# usb2can.net
KiCad netlist of a schematic drawn in EasyEDA Pro
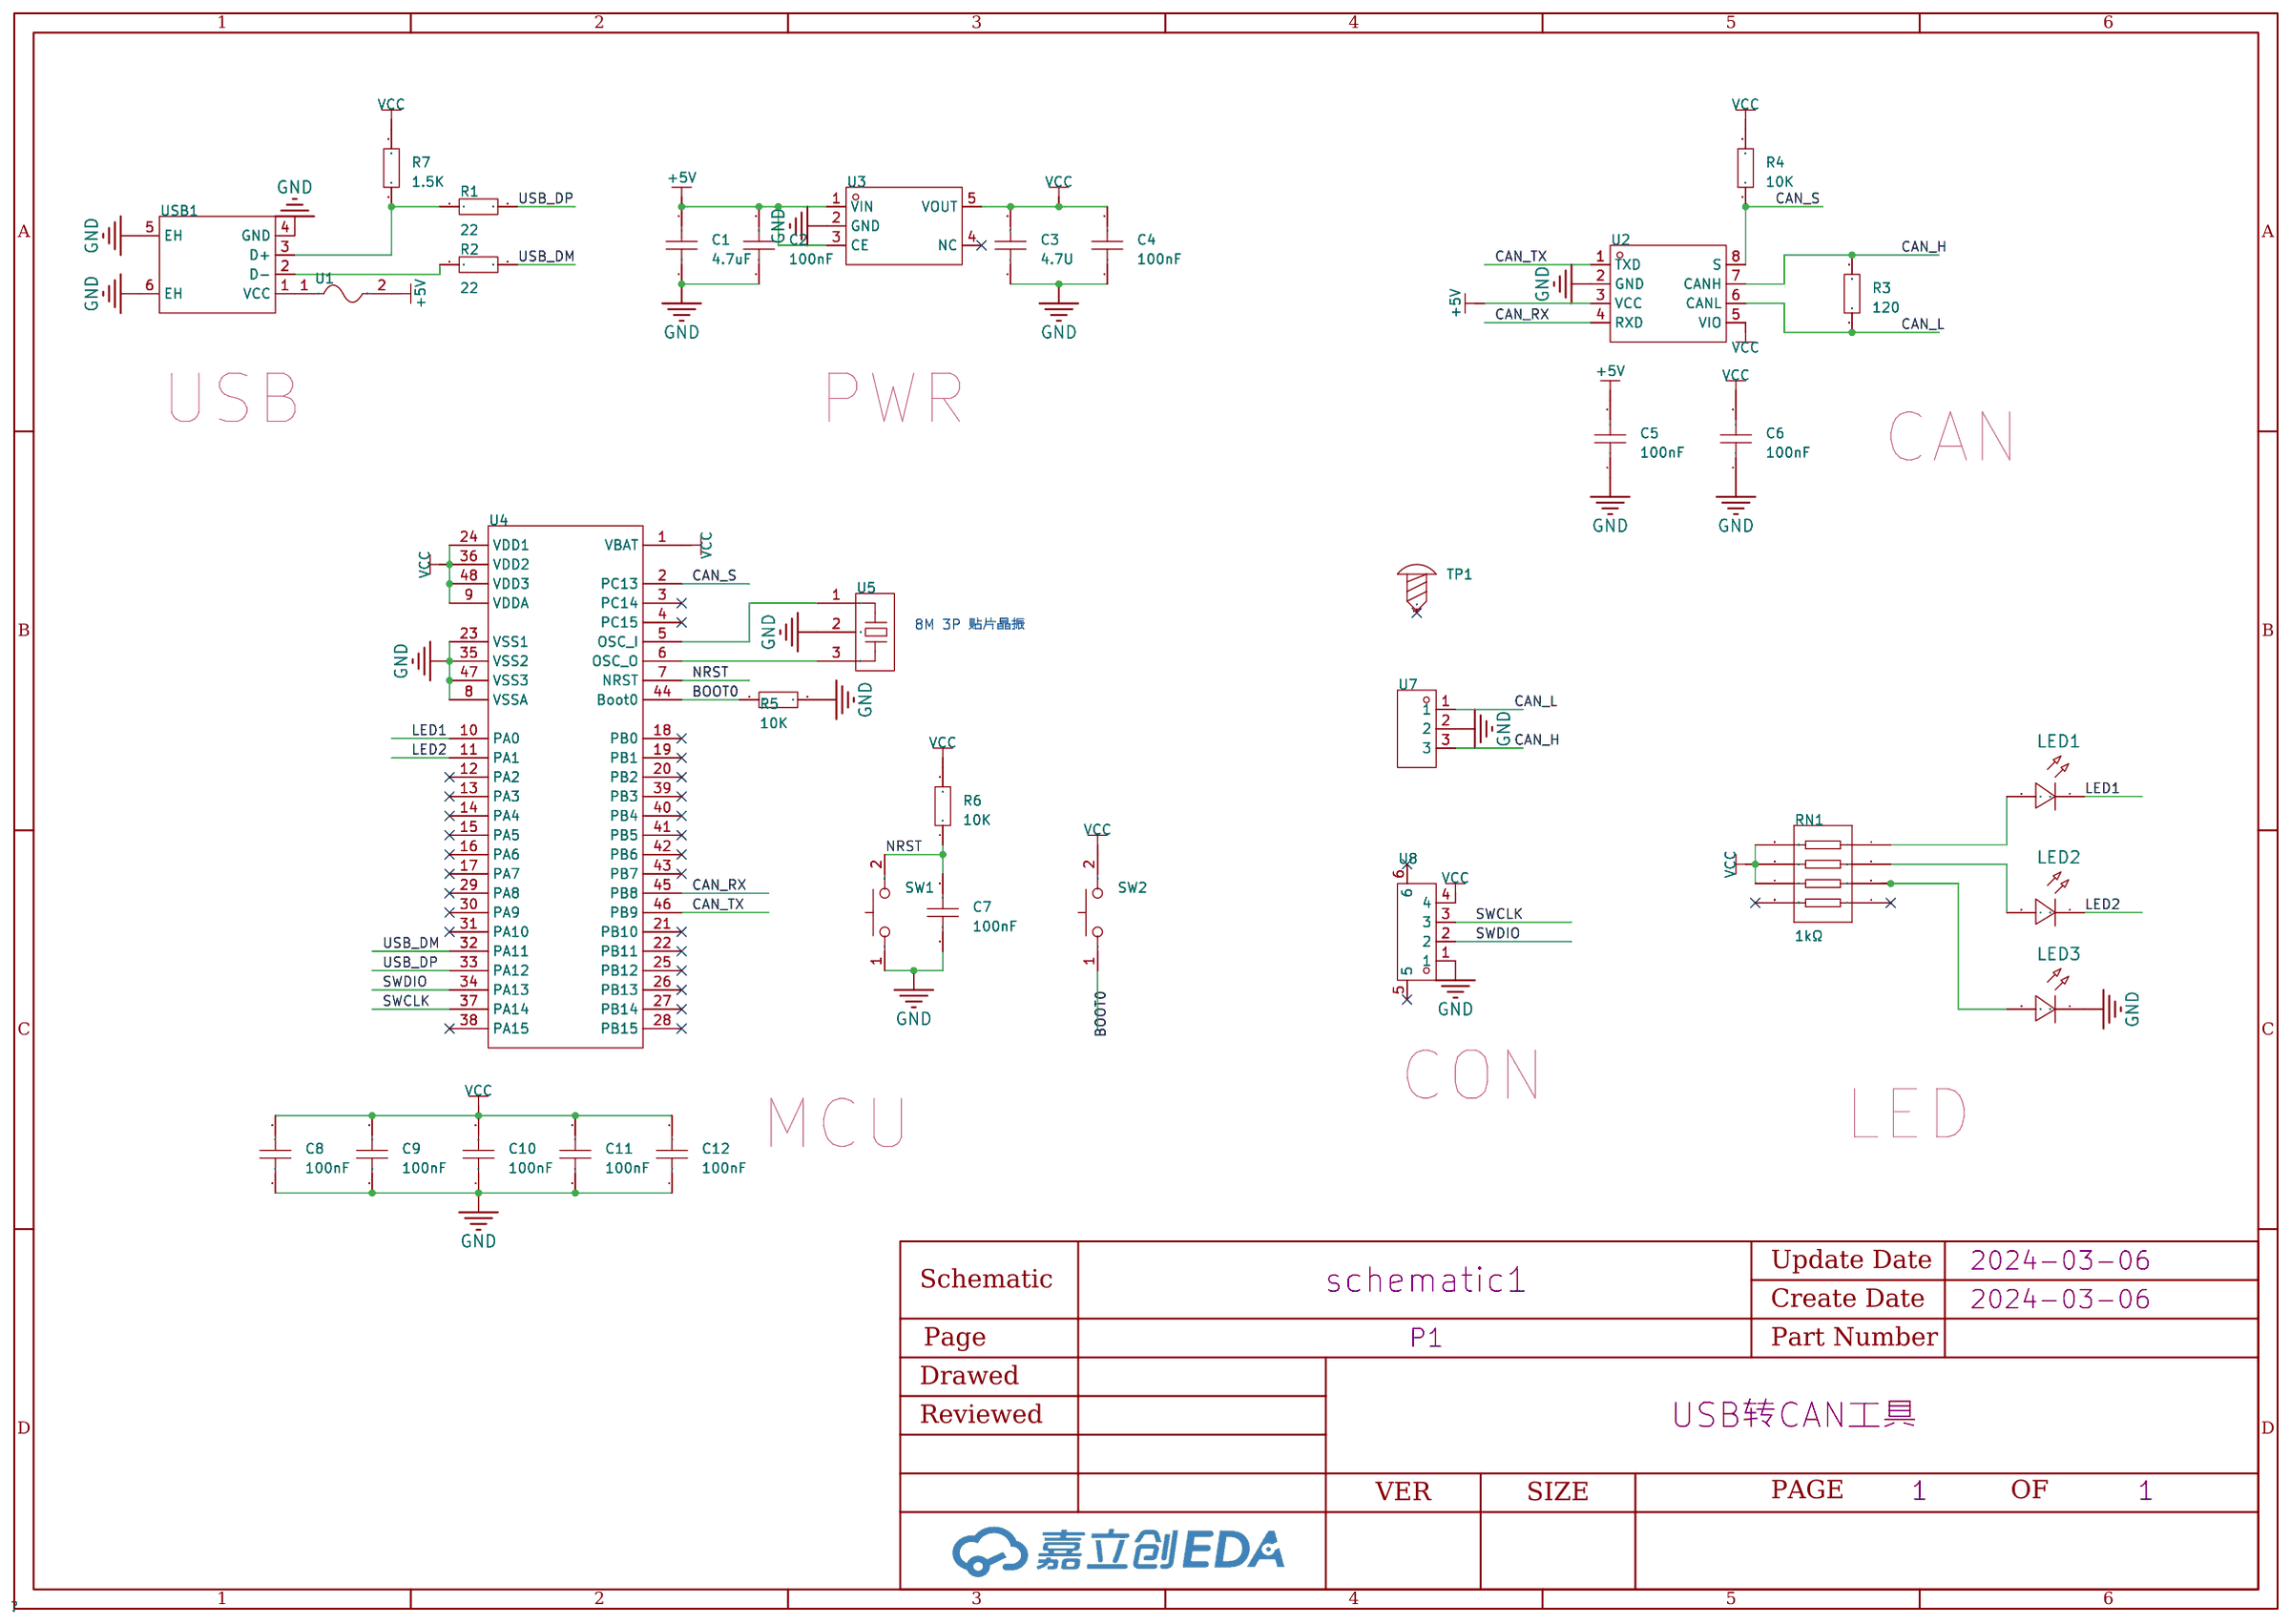
[diagram p0: schematic sheet]

(export (version "E")
  (design (tool "Eeschema 10.0.6"))
  (components
    (comp (ref "C1")
      (value "4.7uF")
      (footprint "easyedapro:C0402")
      (libsource (lib "easyedapro") (part "CapAcitance"))
    )
    (comp (ref "C2")
      (value "100nF")
      (footprint "easyedapro:C0402")
      (libsource (lib "easyedapro") (part "CapAcitance"))
    )
    (comp (ref "C3")
      (value "4.7U")
      (footprint "easyedapro:C0402")
      (libsource (lib "easyedapro") (part "CapAcitance"))
    )
    (comp (ref "C4")
      (value "100nF")
      (footprint "easyedapro:C0402")
      (libsource (lib "easyedapro") (part "CapAcitance"))
    )
    (comp (ref "C5")
      (value "100nF")
      (footprint "easyedapro:C0402")
      (libsource (lib "easyedapro") (part "CapAcitance"))
    )
    (comp (ref "C6")
      (value "100nF")
      (footprint "easyedapro:C0402")
      (libsource (lib "easyedapro") (part "CapAcitance"))
    )
    (comp (ref "C7")
      (value "100nF")
      (footprint "easyedapro:C0402")
      (libsource (lib "easyedapro") (part "CapAcitance"))
    )
    (comp (ref "C8")
      (value "100nF")
      (footprint "easyedapro:C0402")
      (libsource (lib "easyedapro") (part "CapAcitance"))
    )
    (comp (ref "C9")
      (value "100nF")
      (footprint "easyedapro:C0402")
      (libsource (lib "easyedapro") (part "CapAcitance"))
    )
    (comp (ref "C10")
      (value "100nF")
      (footprint "easyedapro:C0402")
      (libsource (lib "easyedapro") (part "CapAcitance"))
    )
    (comp (ref "C11")
      (value "100nF")
      (footprint "easyedapro:C0402")
      (libsource (lib "easyedapro") (part "CapAcitance"))
    )
    (comp (ref "C12")
      (value "100nF")
      (footprint "easyedapro:C0402")
      (libsource (lib "easyedapro") (part "CapAcitance"))
    )
    (comp (ref "LED1")
      (value "~")
      (footprint "easyedapro:LED_0402")
      (libsource (lib "easyedapro") (part "LED_R"))
    )
    (comp (ref "LED2")
      (value "~")
      (footprint "easyedapro:LED_0402")
      (libsource (lib "easyedapro") (part "LED_R"))
    )
    (comp (ref "LED3")
      (value "~")
      (footprint "easyedapro:LED_0402")
      (libsource (lib "easyedapro") (part "LED_R"))
    )
    (comp (ref "R1") (value "22") (footprint "easyedapro:R0402") (libsource (lib "easyedapro") (part "电阻")))
    (comp (ref "R2") (value "22") (footprint "easyedapro:R0402") (libsource (lib "easyedapro") (part "电阻")))
    (comp (ref "R3") (value "120") (footprint "easyedapro:R0402") (libsource (lib "easyedapro") (part "电阻")))
    (comp (ref "R4") (value "10K") (footprint "easyedapro:R0402") (libsource (lib "easyedapro") (part "电阻")))
    (comp (ref "R5") (value "10K") (footprint "easyedapro:R0402") (libsource (lib "easyedapro") (part "电阻")))
    (comp (ref "R6") (value "10K") (footprint "easyedapro:R0402") (libsource (lib "easyedapro") (part "电阻")))
    (comp (ref "R7") (value "1.5K") (footprint "easyedapro:R0402") (libsource (lib "easyedapro") (part "电阻")))
    (comp (ref "RN1")
      (value "1kΩ")
      (footprint "easyedapro:RES-ARRAY-SMD_0804-8P-L2.0-W1.0-BL")
      (description "阻值:1kΩ;精度:±5%;单个元件功率:62.5mW;温度系数:±200ppm/°C;电阻器数:4;引脚数:8;")
      (fields (field (name "Manufacturer Part") "YC124-JR-071KL") (field (name "Manufacturer") "YAGEO(国巨)"))
      (libsource (lib "easyedapro") (part "YC124-JR-071KL"))
    )
    (comp (ref "SW1")
      (value "SKRKAEE020")
      (footprint "easyedapro:SW-SMD_L3.9-W3.0-P4.45")
      (description "触点电流:50mA;额定电压(DC):12V;电路结构:单刀单掷;按钮作用方向:顶部触动;致动器样式:圆形按钮;照明颜色:-;开关长度:3.9mm;开关宽度:2.9mm;开关高度:2mm;")
      (fields (field (name "Manufacturer") "ALPSALPINE(阿尔卑斯阿尔派)"))
      (libsource (lib "easyedapro") (part "SKRKAEE020"))
    )
    (comp (ref "SW2")
      (value "SKRKAEE020")
      (footprint "easyedapro:SW-SMD_L3.9-W3.0-P4.45")
      (description "触点电流:50mA;额定电压(DC):12V;电路结构:单刀单掷;按钮作用方向:顶部触动;致动器样式:圆形按钮;照明颜色:-;开关长度:3.9mm;开关宽度:2.9mm;开关高度:2mm;")
      (fields (field (name "Manufacturer") "ALPSALPINE(阿尔卑斯阿尔派)"))
      (libsource (lib "easyedapro") (part "SKRKAEE020"))
    )
    (comp (ref "TP1") (value "~") (footprint "easyedapro:M3螺丝") (libsource (lib "easyedapro") (part "M3螺丝")))
    (comp (ref "U1")
      (value "MF-PSMF020X-2")
      (footprint "easyedapro:F0805")
      (fields (field (name "Manufacturer") "BOURNS"))
      (libsource (lib "easyedapro") (part "MF-PSMF020X-2"))
    )
    (comp (ref "U2")
      (value "TJA1051T/3")
      (footprint "easyedapro:SOP-8_L4.9-W3.9-P1.27-LS6.0-BL-1")
      (fields (field (name "Manufacturer") "Tokmas(托克马斯)"))
      (libsource (lib "easyedapro") (part "TJA1051T/3"))
    )
    (comp (ref "U3")
      (value "TPRT9013-33GB")
      (footprint "easyedapro:SOT-23-5_L3.0-W1.7-P0.95-LS2.8-BL")
      (description "输出类型:-;")
      (fields (field (name "Manufacturer") "TECH PUBLIC(台舟)"))
      (libsource (lib "easyedapro") (part "TPRT9013-33GB"))
    )
    (comp (ref "U4")
      (value "STM32F072C8T6")
      (footprint "easyedapro:LQFP-48_L7.0-W7.0-P0.50-LS9.0-BL")
      (description "工作电压:1.65V ~ 3.6V;CPU内核:ARM® Cortex®-M0;")
      (fields (field (name "Manufacturer") "ST(意法半导体)"))
      (libsource (lib "easyedapro") (part "STM32F072C8T6"))
    )
    (comp (ref "U5")
      (value "CSTCE8M0V53-R0")
      (footprint "easyedapro:OSC-SMD_3P-L3.2-W1.3-P1.2-L")
      (libsource (lib "easyedapro") (part "CSTCE8M0V53-R0"))
    )
    (comp (ref "U7")
      (value "KF350-3.5-3P")
      (footprint "easyedapro:CONN-TH_3P-P3.50_KF350-3.5-3P")
      (fields (field (name "Manufacturer") "KEFA(科发)"))
      (libsource (lib "easyedapro") (part "KF350-3.5-3P"))
    )
    (comp (ref "U8")
      (value "SH1.0-4P")
      (footprint "easyedapro:CONN-SMD_4P-P1.00_SH1.0-4P")
      (libsource (lib "easyedapro") (part "SH1.0-4P"))
    )
    (comp (ref "USB1")
      (value "480370001")
      (footprint "easyedapro:USB-A-TH_48037-0001")
      (description "连接器类型:Type-A;标准:USB 2;公母:公头;触点数量:4;端口数量:1;")
      (fields (field (name "Manufacturer") "MOLEX"))
      (libsource (lib "easyedapro") (part "48037-0001"))
    )
  )
  (nets
    (net (code "1") (name "+5V") (class "Default")
      (node (ref "C1") (pin "2") (pinfunction "2_2") (pintype "input"))
      (node (ref "C2") (pin "2") (pinfunction "2_2") (pintype "input"))
      (node (ref "C5") (pin "2") (pinfunction "2_2") (pintype "input"))
      (node (ref "U1") (pin "2") (pinfunction "2_2") (pintype "input"))
      (node (ref "U2") (pin "3") (pinfunction "VCC_3") (pintype "input"))
      (node (ref "U3") (pin "1") (pinfunction "VIN_1") (pintype "input"))
      (node (ref "U3") (pin "3") (pinfunction "CE_3") (pintype "input"))
    )
    (net (code "2") (name "/BOOT0") (class "Default")
      (node (ref "R5") (pin "1") (pinfunction "1_1") (pintype "input"))
      (node (ref "SW2") (pin "1") (pinfunction "1_1") (pintype "input"))
      (node (ref "U4") (pin "44") (pinfunction "Boot0_44") (pintype "input"))
    )
    (net (code "3") (name "/CAN_H") (class "Default")
      (node (ref "R3") (pin "2") (pinfunction "2_2") (pintype "input"))
      (node (ref "U2") (pin "7") (pinfunction "CANH_7") (pintype "input"))
      (node (ref "U7") (pin "3") (pinfunction "3_3") (pintype "input"))
    )
    (net (code "4") (name "/CAN_L") (class "Default")
      (node (ref "R3") (pin "1") (pinfunction "1_1") (pintype "input"))
      (node (ref "U2") (pin "6") (pinfunction "CANL_6") (pintype "input"))
      (node (ref "U7") (pin "1") (pinfunction "1_1") (pintype "input"))
    )
    (net (code "5") (name "/CAN_RX") (class "Default")
      (node (ref "U2") (pin "4") (pinfunction "RXD_4") (pintype "input"))
      (node (ref "U4") (pin "45") (pinfunction "PB8_45") (pintype "input"))
    )
    (net (code "6") (name "/CAN_S") (class "Default")
      (node (ref "R4") (pin "1") (pinfunction "1_1") (pintype "input"))
      (node (ref "U2") (pin "8") (pinfunction "S_8") (pintype "input"))
      (node (ref "U4") (pin "2") (pinfunction "PC13_2") (pintype "input"))
    )
    (net (code "7") (name "/CAN_TX") (class "Default")
      (node (ref "U2") (pin "1") (pinfunction "TXD_1") (pintype "input"))
      (node (ref "U4") (pin "46") (pinfunction "PB9_46") (pintype "input"))
    )
    (net (code "8") (name "/LED1") (class "Default")
      (node (ref "LED1") (pin "1") (pinfunction "C_1") (pintype "input"))
      (node (ref "U4") (pin "10") (pinfunction "PA0_10") (pintype "input"))
    )
    (net (code "9") (name "/LED2") (class "Default")
      (node (ref "LED2") (pin "1") (pinfunction "C_1") (pintype "input"))
      (node (ref "U4") (pin "11") (pinfunction "PA1_11") (pintype "input"))
    )
    (net (code "10") (name "/NRST") (class "Default")
      (node (ref "C7") (pin "2") (pinfunction "2_2") (pintype "input"))
      (node (ref "R6") (pin "1") (pinfunction "1_1") (pintype "input"))
      (node (ref "SW1") (pin "2") (pinfunction "2_2") (pintype "input"))
      (node (ref "U4") (pin "7") (pinfunction "NRST_7") (pintype "input"))
    )
    (net (code "11") (name "/SWCLK") (class "Default")
      (node (ref "U4") (pin "37") (pinfunction "PA14_37") (pintype "input"))
      (node (ref "U8") (pin "3") (pinfunction "3_3") (pintype "input"))
    )
    (net (code "12") (name "/SWDIO") (class "Default")
      (node (ref "U4") (pin "34") (pinfunction "PA13_34") (pintype "input"))
      (node (ref "U8") (pin "2") (pinfunction "2_2") (pintype "input"))
    )
    (net (code "13") (name "/USB_DM") (class "Default")
      (node (ref "R2") (pin "2") (pinfunction "2_2") (pintype "input"))
      (node (ref "U4") (pin "32") (pinfunction "PA11_32") (pintype "input"))
    )
    (net (code "14") (name "/USB_DP") (class "Default")
      (node (ref "R1") (pin "2") (pinfunction "2_2") (pintype "input"))
      (node (ref "U4") (pin "33") (pinfunction "PA12_33") (pintype "input"))
    )
    (net (code "15") (name "GND") (class "Default")
      (node (ref "C1") (pin "1") (pinfunction "1_1") (pintype "input"))
      (node (ref "C10") (pin "1") (pinfunction "1_1") (pintype "input"))
      (node (ref "C11") (pin "1") (pinfunction "1_1") (pintype "input"))
      (node (ref "C12") (pin "1") (pinfunction "1_1") (pintype "input"))
      (node (ref "C2") (pin "1") (pinfunction "1_1") (pintype "input"))
      (node (ref "C3") (pin "1") (pinfunction "1_1") (pintype "input"))
      (node (ref "C4") (pin "1") (pinfunction "1_1") (pintype "input"))
      (node (ref "C5") (pin "1") (pinfunction "1_1") (pintype "input"))
      (node (ref "C6") (pin "1") (pinfunction "1_1") (pintype "input"))
      (node (ref "C7") (pin "1") (pinfunction "1_1") (pintype "input"))
      (node (ref "C8") (pin "1") (pinfunction "1_1") (pintype "input"))
      (node (ref "C9") (pin "1") (pinfunction "1_1") (pintype "input"))
      (node (ref "LED3") (pin "1") (pinfunction "C_1") (pintype "input"))
      (node (ref "R5") (pin "2") (pinfunction "2_2") (pintype "input"))
      (node (ref "SW1") (pin "1") (pinfunction "1_1") (pintype "input"))
      (node (ref "U2") (pin "2") (pinfunction "GND_2") (pintype "input"))
      (node (ref "U3") (pin "2") (pinfunction "GND_2") (pintype "input"))
      (node (ref "U4") (pin "23") (pinfunction "VSS1_23") (pintype "input"))
      (node (ref "U4") (pin "35") (pinfunction "VSS2_35") (pintype "input"))
      (node (ref "U4") (pin "47") (pinfunction "VSS3_47") (pintype "input"))
      (node (ref "U4") (pin "8") (pinfunction "VSSA_8") (pintype "input"))
      (node (ref "U5") (pin "2") (pinfunction "2_2") (pintype "input"))
      (node (ref "U7") (pin "2") (pinfunction "2_2") (pintype "input"))
      (node (ref "U8") (pin "1") (pinfunction "1_1") (pintype "input"))
      (node (ref "USB1") (pin "4") (pinfunction "GND_4") (pintype "input"))
      (node (ref "USB1") (pin "5") (pinfunction "EH_5") (pintype "input"))
      (node (ref "USB1") (pin "6") (pinfunction "EH_6") (pintype "input"))
    )
    (net (code "16") (name "Net-(LED1-A)") (class "Default")
      (node (ref "LED1") (pin "2") (pinfunction "A_2") (pintype "input"))
      (node (ref "RN1") (pin "4") (pinfunction "4_4") (pintype "input"))
    )
    (net (code "17") (name "Net-(LED2-A)") (class "Default")
      (node (ref "LED2") (pin "2") (pinfunction "A_2") (pintype "input"))
      (node (ref "RN1") (pin "3") (pinfunction "3_3") (pintype "input"))
    )
    (net (code "18") (name "Net-(LED3-A)") (class "Default")
      (node (ref "LED3") (pin "2") (pinfunction "A_2") (pintype "input"))
      (node (ref "RN1") (pin "2") (pinfunction "2_2") (pintype "input"))
    )
    (net (code "19") (name "Net-(U4-OSC_I)") (class "Default")
      (node (ref "U4") (pin "5") (pinfunction "OSC_I_5") (pintype "input"))
      (node (ref "U5") (pin "1") (pinfunction "1_1") (pintype "input"))
    )
    (net (code "20") (name "Net-(U4-OSC_O)") (class "Default")
      (node (ref "U4") (pin "6") (pinfunction "OSC_O_6") (pintype "input"))
      (node (ref "U5") (pin "3") (pinfunction "3_3") (pintype "input"))
    )
    (net (code "21") (name "Net-(USB1-D+)") (class "Default")
      (node (ref "R1") (pin "1") (pinfunction "1_1") (pintype "input"))
      (node (ref "R7") (pin "1") (pinfunction "1_1") (pintype "input"))
      (node (ref "USB1") (pin "3") (pinfunction "D+_3") (pintype "input"))
    )
    (net (code "22") (name "Net-(USB1-D-)") (class "Default")
      (node (ref "R2") (pin "1") (pinfunction "1_1") (pintype "input"))
      (node (ref "USB1") (pin "2") (pinfunction "D-_2") (pintype "input"))
    )
    (net (code "23") (name "Net-(USB1-VCC)") (class "Default")
      (node (ref "U1") (pin "1") (pinfunction "1_1") (pintype "input"))
      (node (ref "USB1") (pin "1") (pinfunction "VCC_1") (pintype "input"))
    )
    (net (code "24") (name "VCC") (class "Default")
      (node (ref "C10") (pin "2") (pinfunction "2_2") (pintype "input"))
      (node (ref "C11") (pin "2") (pinfunction "2_2") (pintype "input"))
      (node (ref "C12") (pin "2") (pinfunction "2_2") (pintype "input"))
      (node (ref "C3") (pin "2") (pinfunction "2_2") (pintype "input"))
      (node (ref "C4") (pin "2") (pinfunction "2_2") (pintype "input"))
      (node (ref "C6") (pin "2") (pinfunction "2_2") (pintype "input"))
      (node (ref "C8") (pin "2") (pinfunction "2_2") (pintype "input"))
      (node (ref "C9") (pin "2") (pinfunction "2_2") (pintype "input"))
      (node (ref "R4") (pin "2") (pinfunction "2_2") (pintype "input"))
      (node (ref "R6") (pin "2") (pinfunction "2_2") (pintype "input"))
      (node (ref "R7") (pin "2") (pinfunction "2_2") (pintype "input"))
      (node (ref "RN1") (pin "5") (pinfunction "5_5") (pintype "input"))
      (node (ref "RN1") (pin "6") (pinfunction "6_6") (pintype "input"))
      (node (ref "RN1") (pin "7") (pinfunction "7_7") (pintype "input"))
      (node (ref "SW2") (pin "2") (pinfunction "2_2") (pintype "input"))
      (node (ref "U2") (pin "5") (pinfunction "VIO_5") (pintype "input"))
      (node (ref "U3") (pin "5") (pinfunction "VOUT_5") (pintype "input"))
      (node (ref "U4") (pin "1") (pinfunction "VBAT_1") (pintype "input"))
      (node (ref "U4") (pin "24") (pinfunction "VDD1_24") (pintype "input"))
      (node (ref "U4") (pin "36") (pinfunction "VDD2_36") (pintype "input"))
      (node (ref "U4") (pin "48") (pinfunction "VDD3_48") (pintype "input"))
      (node (ref "U4") (pin "9") (pinfunction "VDDA_9") (pintype "input"))
      (node (ref "U8") (pin "4") (pinfunction "4_4") (pintype "input"))
    )
    (net (code "25") (name "unconnected-(RN1-Pad1)") (class "Default")
      (node (ref "RN1") (pin "1") (pinfunction "1_1") (pintype "input+no_connect"))
    )
    (net (code "26") (name "unconnected-(RN1-Pad8)") (class "Default")
      (node (ref "RN1") (pin "8") (pinfunction "8_8") (pintype "input+no_connect"))
    )
    (net (code "27") (name "unconnected-(TP1-Pad1)") (class "Default")
      (node (ref "TP1") (pin "1") (pinfunction "1_1") (pintype "input+no_connect"))
    )
    (net (code "28") (name "unconnected-(U3-NC-Pad4)") (class "Default")
      (node (ref "U3") (pin "4") (pinfunction "NC_4") (pintype "input+no_connect"))
    )
    (net (code "29") (name "unconnected-(U4-PA2-Pad12)") (class "Default")
      (node (ref "U4") (pin "12") (pinfunction "PA2_12") (pintype "input+no_connect"))
    )
    (net (code "30") (name "unconnected-(U4-PA3-Pad13)") (class "Default")
      (node (ref "U4") (pin "13") (pinfunction "PA3_13") (pintype "input+no_connect"))
    )
    (net (code "31") (name "unconnected-(U4-PA4-Pad14)") (class "Default")
      (node (ref "U4") (pin "14") (pinfunction "PA4_14") (pintype "input+no_connect"))
    )
    (net (code "32") (name "unconnected-(U4-PA5-Pad15)") (class "Default")
      (node (ref "U4") (pin "15") (pinfunction "PA5_15") (pintype "input+no_connect"))
    )
    (net (code "33") (name "unconnected-(U4-PA6-Pad16)") (class "Default")
      (node (ref "U4") (pin "16") (pinfunction "PA6_16") (pintype "input+no_connect"))
    )
    (net (code "34") (name "unconnected-(U4-PA7-Pad17)") (class "Default")
      (node (ref "U4") (pin "17") (pinfunction "PA7_17") (pintype "input+no_connect"))
    )
    (net (code "35") (name "unconnected-(U4-PA8-Pad29)") (class "Default")
      (node (ref "U4") (pin "29") (pinfunction "PA8_29") (pintype "input+no_connect"))
    )
    (net (code "36") (name "unconnected-(U4-PA9-Pad30)") (class "Default")
      (node (ref "U4") (pin "30") (pinfunction "PA9_30") (pintype "input+no_connect"))
    )
    (net (code "37") (name "unconnected-(U4-PA10-Pad31)") (class "Default")
      (node (ref "U4") (pin "31") (pinfunction "PA10_31") (pintype "input+no_connect"))
    )
    (net (code "38") (name "unconnected-(U4-PA15-Pad38)") (class "Default")
      (node (ref "U4") (pin "38") (pinfunction "PA15_38") (pintype "input+no_connect"))
    )
    (net (code "39") (name "unconnected-(U4-PB0-Pad18)") (class "Default")
      (node (ref "U4") (pin "18") (pinfunction "PB0_18") (pintype "input+no_connect"))
    )
    (net (code "40") (name "unconnected-(U4-PB1-Pad19)") (class "Default")
      (node (ref "U4") (pin "19") (pinfunction "PB1_19") (pintype "input+no_connect"))
    )
    (net (code "41") (name "unconnected-(U4-PB2-Pad20)") (class "Default")
      (node (ref "U4") (pin "20") (pinfunction "PB2_20") (pintype "input+no_connect"))
    )
    (net (code "42") (name "unconnected-(U4-PB3-Pad39)") (class "Default")
      (node (ref "U4") (pin "39") (pinfunction "PB3_39") (pintype "input+no_connect"))
    )
    (net (code "43") (name "unconnected-(U4-PB4-Pad40)") (class "Default")
      (node (ref "U4") (pin "40") (pinfunction "PB4_40") (pintype "input+no_connect"))
    )
    (net (code "44") (name "unconnected-(U4-PB5-Pad41)") (class "Default")
      (node (ref "U4") (pin "41") (pinfunction "PB5_41") (pintype "input+no_connect"))
    )
    (net (code "45") (name "unconnected-(U4-PB6-Pad42)") (class "Default")
      (node (ref "U4") (pin "42") (pinfunction "PB6_42") (pintype "input+no_connect"))
    )
    (net (code "46") (name "unconnected-(U4-PB7-Pad43)") (class "Default")
      (node (ref "U4") (pin "43") (pinfunction "PB7_43") (pintype "input+no_connect"))
    )
    (net (code "47") (name "unconnected-(U4-PB10-Pad21)") (class "Default")
      (node (ref "U4") (pin "21") (pinfunction "PB10_21") (pintype "input+no_connect"))
    )
    (net (code "48") (name "unconnected-(U4-PB11-Pad22)") (class "Default")
      (node (ref "U4") (pin "22") (pinfunction "PB11_22") (pintype "input+no_connect"))
    )
    (net (code "49") (name "unconnected-(U4-PB12-Pad25)") (class "Default")
      (node (ref "U4") (pin "25") (pinfunction "PB12_25") (pintype "input+no_connect"))
    )
    (net (code "50") (name "unconnected-(U4-PB13-Pad26)") (class "Default")
      (node (ref "U4") (pin "26") (pinfunction "PB13_26") (pintype "input+no_connect"))
    )
    (net (code "51") (name "unconnected-(U4-PB14-Pad27)") (class "Default")
      (node (ref "U4") (pin "27") (pinfunction "PB14_27") (pintype "input+no_connect"))
    )
    (net (code "52") (name "unconnected-(U4-PB15-Pad28)") (class "Default")
      (node (ref "U4") (pin "28") (pinfunction "PB15_28") (pintype "input+no_connect"))
    )
    (net (code "53") (name "unconnected-(U4-PC14-Pad3)") (class "Default")
      (node (ref "U4") (pin "3") (pinfunction "PC14_3") (pintype "input+no_connect"))
    )
    (net (code "54") (name "unconnected-(U4-PC15-Pad4)") (class "Default")
      (node (ref "U4") (pin "4") (pinfunction "PC15_4") (pintype "input+no_connect"))
    )
    (net (code "55") (name "unconnected-(U8-Pad5)") (class "Default")
      (node (ref "U8") (pin "5") (pinfunction "5_5") (pintype "input+no_connect"))
    )
    (net (code "56") (name "unconnected-(U8-Pad6)") (class "Default")
      (node (ref "U8") (pin "6") (pinfunction "6_6") (pintype "input+no_connect"))
    )
  )
)
